# Valve.net
KiCad netlist of a schematic drawn in Altium Designer
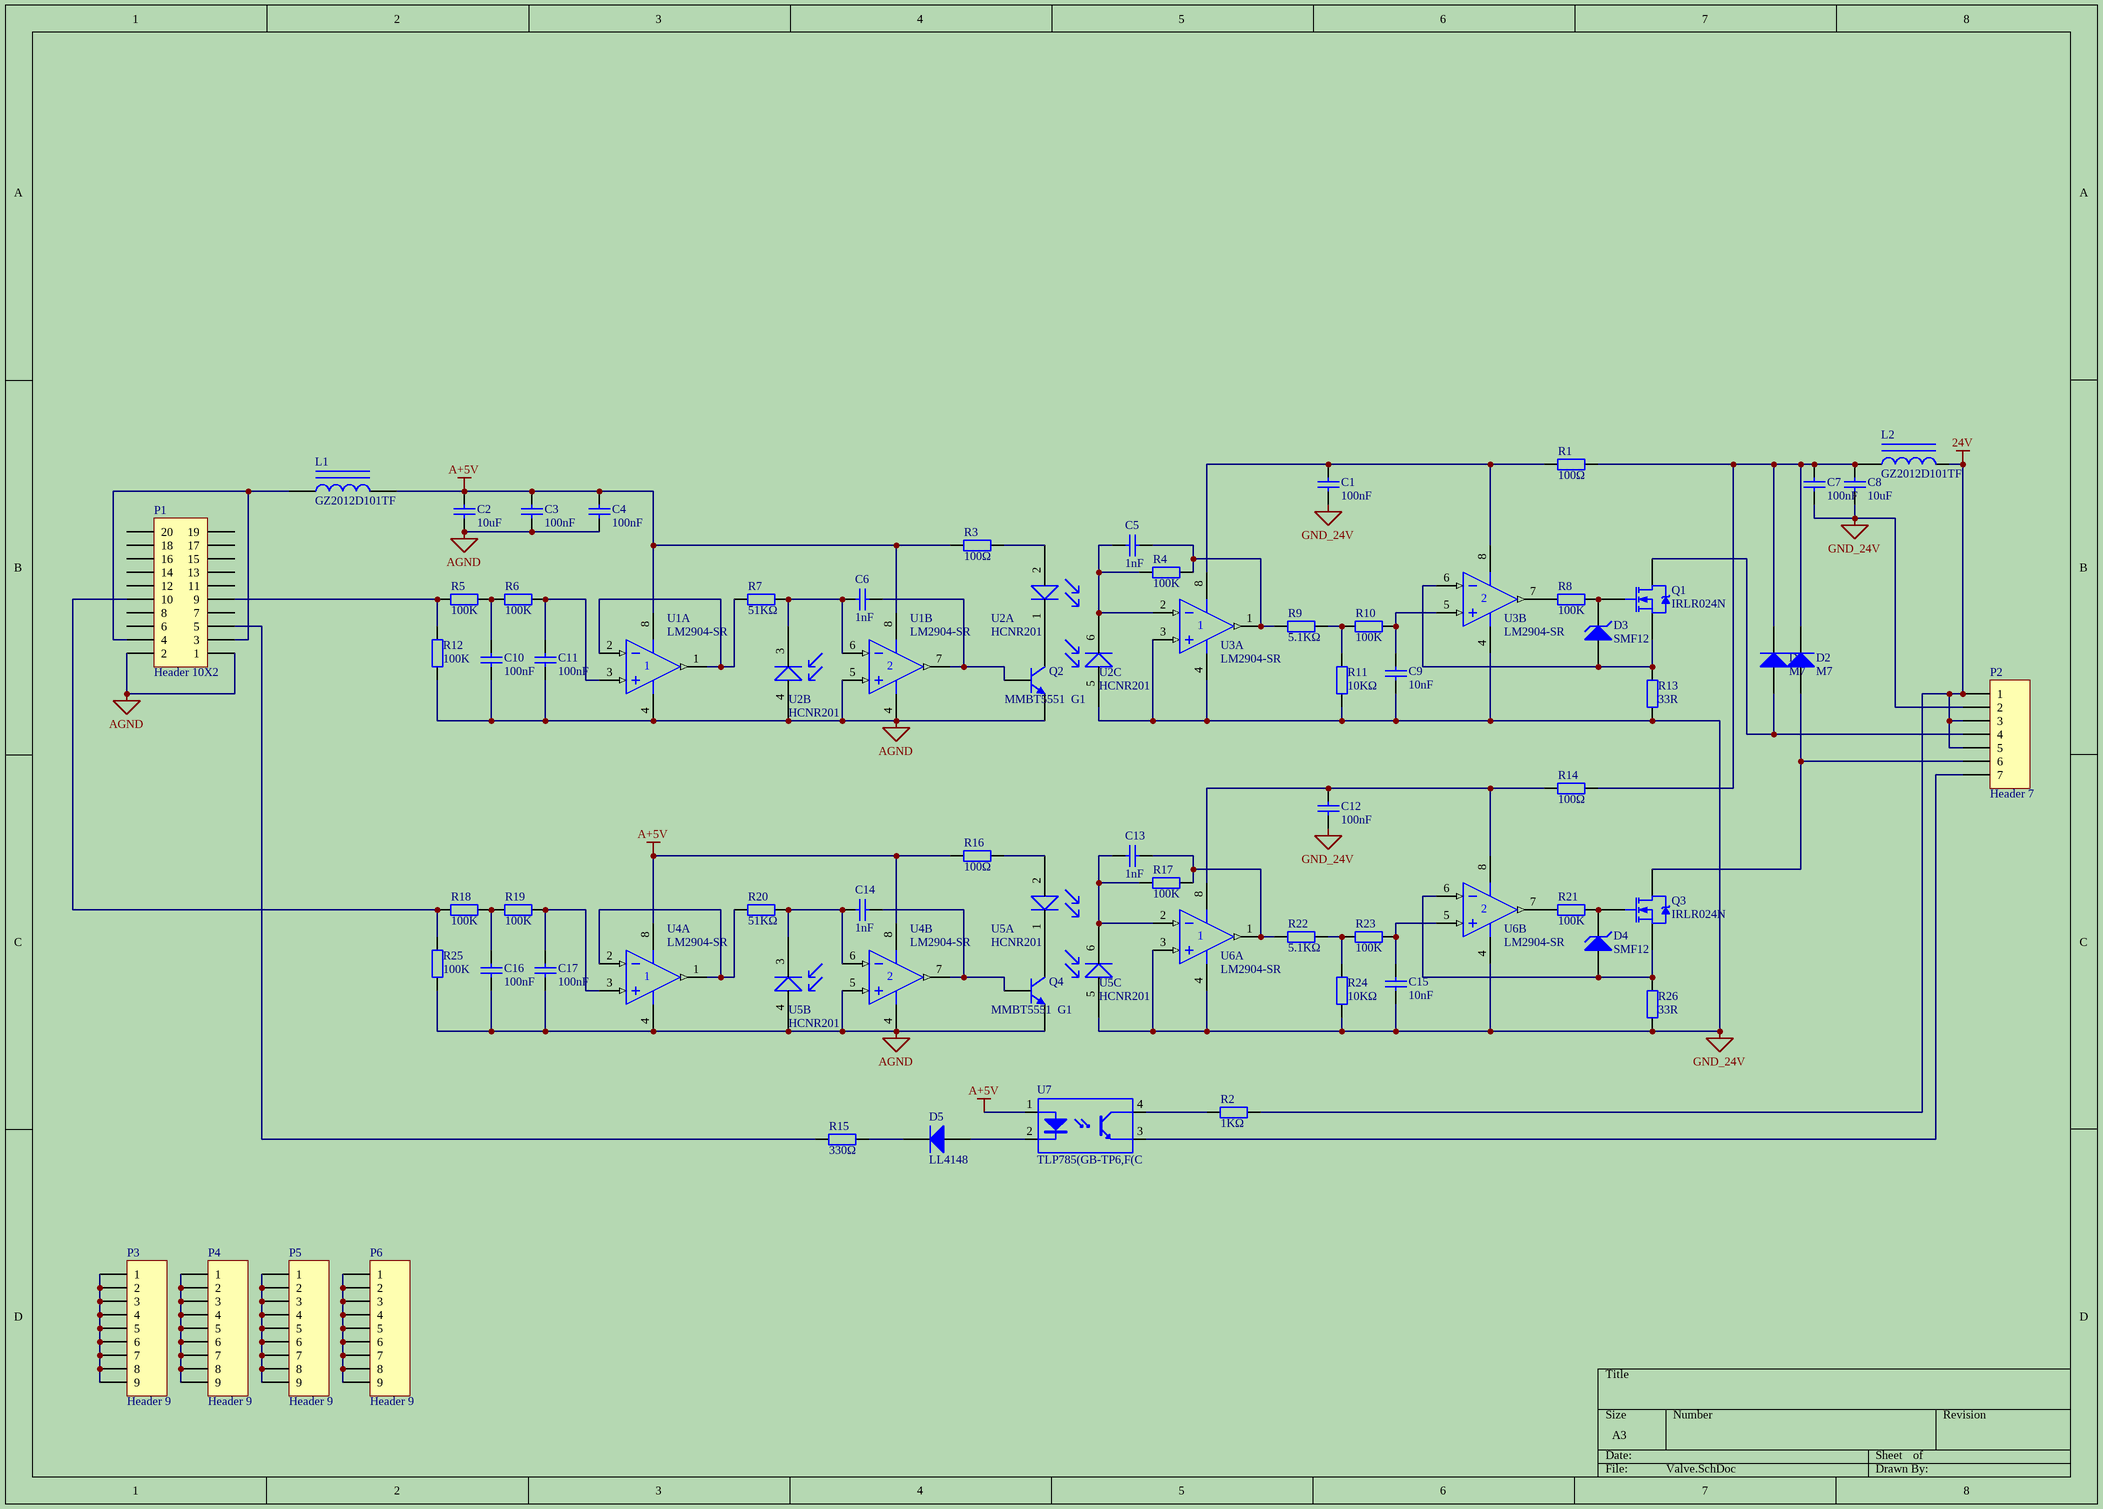
[diagram p0: Valve.SchDoc]

(export (version "E")
  (design (tool "Eeschema 10.0.6"))
  (components
    (comp (ref "C1")
      (value "100nF")
      (footprint "0805_C")
      (description "贴片电容")
      (libsource (lib "Miscellaneous Devices LC") (part "0805 100nF(104) 10% 50V"))
    )
    (comp (ref "C2")
      (value "10uF")
      (footprint "1206_C")
      (description "贴片电容")
      (libsource (lib "Miscellaneous Devices LC") (part "1206 10uF (106) 10% 50V"))
    )
    (comp (ref "C3")
      (value "100nF")
      (footprint "0805_C")
      (description "贴片电容")
      (libsource (lib "Miscellaneous Devices LC") (part "0805 100nF(104) 10% 50V"))
    )
    (comp (ref "C4")
      (value "100nF")
      (footprint "0805_C")
      (description "贴片电容")
      (libsource (lib "Miscellaneous Devices LC") (part "0805 100nF(104) 10% 50V"))
    )
    (comp (ref "C5")
      (value "1nF")
      (footprint "0805_C")
      (description "贴片电容")
      (libsource (lib "Miscellaneous Devices LC") (part "0805 1nF (102) 10% 50V"))
    )
    (comp (ref "C6")
      (value "1nF")
      (footprint "0805_C")
      (description "贴片电容")
      (libsource (lib "Miscellaneous Devices LC") (part "0805 1nF (102) 10% 50V"))
    )
    (comp (ref "C7")
      (value "100nF")
      (footprint "0805_C")
      (description "贴片电容")
      (libsource (lib "Miscellaneous Devices LC") (part "0805 100nF(104) 10% 50V"))
    )
    (comp (ref "C8")
      (value "10uF")
      (footprint "1206_C")
      (description "贴片电容")
      (libsource (lib "Miscellaneous Devices LC") (part "1206 10uF (106) 10% 50V"))
    )
    (comp (ref "C9")
      (value "10nF")
      (footprint "0805_C")
      (description "贴片电容")
      (libsource (lib "Miscellaneous Devices LC") (part "0805 10nF (103) 10% 50V"))
    )
    (comp (ref "C10")
      (value "100nF")
      (footprint "0805_C")
      (description "贴片电容")
      (libsource (lib "Miscellaneous Devices LC") (part "0805 100nF(104) 10% 50V"))
    )
    (comp (ref "C11")
      (value "100nF")
      (footprint "0805_C")
      (description "贴片电容")
      (libsource (lib "Miscellaneous Devices LC") (part "0805 100nF(104) 10% 50V"))
    )
    (comp (ref "C12")
      (value "100nF")
      (footprint "0805_C")
      (description "贴片电容")
      (libsource (lib "Miscellaneous Devices LC") (part "0805 100nF(104) 10% 50V"))
    )
    (comp (ref "C13")
      (value "1nF")
      (footprint "0805_C")
      (description "贴片电容")
      (libsource (lib "Miscellaneous Devices LC") (part "0805 1nF (102) 10% 50V"))
    )
    (comp (ref "C14")
      (value "1nF")
      (footprint "0805_C")
      (description "贴片电容")
      (libsource (lib "Miscellaneous Devices LC") (part "0805 1nF (102) 10% 50V"))
    )
    (comp (ref "C15")
      (value "10nF")
      (footprint "0805_C")
      (description "贴片电容")
      (libsource (lib "Miscellaneous Devices LC") (part "0805 10nF (103) 10% 50V"))
    )
    (comp (ref "C16")
      (value "100nF")
      (footprint "0805_C")
      (description "贴片电容")
      (libsource (lib "Miscellaneous Devices LC") (part "0805 100nF(104) 10% 50V"))
    )
    (comp (ref "C17")
      (value "100nF")
      (footprint "0805_C")
      (description "贴片电容")
      (libsource (lib "Miscellaneous Devices LC") (part "0805 100nF(104) 10% 50V"))
    )
    (comp (ref "D1")
      (value "M7")
      (footprint "SMA(DO-214AC)_S1")
      (description "二极管")
      (libsource (lib "Miscellaneous Devices LC") (part "SMA(DO-214AC) M7"))
    )
    (comp (ref "D2")
      (value "M7")
      (footprint "SMA(DO-214AC)_S1")
      (description "二极管")
      (libsource (lib "Miscellaneous Devices LC") (part "SMA(DO-214AC) M7"))
    )
    (comp (ref "D3")
      (value "SMF12")
      (footprint "SOD-123")
      (description "Zener Diode")
      (fields (field (name "PUBLISHER") "Altium Limited"))
      (libsource (lib "Miscellaneous Devices") (part "D Zener"))
    )
    (comp (ref "D4")
      (value "SMF12")
      (footprint "SOD-123")
      (description "Zener Diode")
      (fields (field (name "PUBLISHER") "Altium Limited"))
      (libsource (lib "Miscellaneous Devices") (part "D Zener"))
    )
    (comp (ref "D5")
      (value "LL4148")
      (footprint "LL-34")
      (description "开关二极管")
      (libsource (lib "Miscellaneous Devices LC") (part "LL-34 LL4148 LL-34 1206"))
    )
    (comp (ref "L1")
      (value "GZ2012D101TF")
      (footprint "0805_L")
      (description "贴片磁珠")
      (libsource (lib "Miscellaneous Devices LC") (part "0805 100Ω 25% 100MHz"))
    )
    (comp (ref "L2")
      (value "GZ2012D101TF")
      (footprint "0805_L")
      (description "贴片磁珠")
      (libsource (lib "Miscellaneous Devices LC") (part "0805 100Ω 25% 100MHz"))
    )
    (comp (ref "P1")
      (value "Header 10X2")
      (footprint "IDC20-EJ")
      (description "Header, 10-Pin, Dual row")
      (fields (field (name "PUBLISHER") "Altium Limited"))
      (libsource (lib "Miscellaneous Connectors") (part "Header 10X2"))
    )
    (comp (ref "P2")
      (value "Header 7")
      (footprint "3.96-7")
      (description "Header, 7-Pin")
      (fields (field (name "PUBLISHER") "Altium Limited"))
      (libsource (lib "Miscellaneous Connectors") (part "Header 7"))
    )
    (comp (ref "P3")
      (value "Header 9")
      (footprint "LK")
      (description "Header, 9-Pin")
      (fields (field (name "PUBLISHER") "Altium Limited"))
      (libsource (lib "Miscellaneous Connectors") (part "Header 9"))
    )
    (comp (ref "P4")
      (value "Header 9")
      (footprint "LK")
      (description "Header, 9-Pin")
      (fields (field (name "PUBLISHER") "Altium Limited"))
      (libsource (lib "Miscellaneous Connectors") (part "Header 9"))
    )
    (comp (ref "P5")
      (value "Header 9")
      (footprint "LK")
      (description "Header, 9-Pin")
      (fields (field (name "PUBLISHER") "Altium Limited"))
      (libsource (lib "Miscellaneous Connectors") (part "Header 9"))
    )
    (comp (ref "P6")
      (value "Header 9")
      (footprint "LK")
      (description "Header, 9-Pin")
      (fields (field (name "PUBLISHER") "Altium Limited"))
      (libsource (lib "Miscellaneous Connectors") (part "Header 9"))
    )
    (comp (ref "Q1")
      (value "IRLR024N")
      (footprint "TO-252AA_N")
      (description "HEXFET Power MOSFET")
      (fields (field (name "PUBLISHER") "Altium Limited"))
      (libsource (lib "IR Discrete MOSFET - Power") (part "IRLR024N"))
    )
    (comp (ref "Q2")
      (value "MMBT5551  G1")
      (footprint "SOT-23(SOT-23-3)")
      (description "三极管")
      (libsource (lib "Miscellaneous Devices LC") (part "SOT-23 MMBT5551  G1"))
    )
    (comp (ref "Q3")
      (value "IRLR024N")
      (footprint "TO-252AA_N")
      (description "HEXFET Power MOSFET")
      (fields (field (name "PUBLISHER") "Altium Limited"))
      (libsource (lib "IR Discrete MOSFET - Power") (part "IRLR024N"))
    )
    (comp (ref "Q4")
      (value "MMBT5551  G1")
      (footprint "SOT-23(SOT-23-3)")
      (description "三极管")
      (libsource (lib "Miscellaneous Devices LC") (part "SOT-23 MMBT5551  G1"))
    )
    (comp (ref "R1")
      (value "100Ω")
      (footprint "0805_R")
      (description "贴片电阻")
      (libsource (lib "Miscellaneous Devices LC") (part "0805 100Ω (1000) 1%"))
    )
    (comp (ref "R2")
      (value "1KΩ")
      (footprint "0805_R")
      (description "贴片电阻")
      (libsource (lib "Miscellaneous Devices LC") (part "0805 1KΩ (1001) 1%"))
    )
    (comp (ref "R3")
      (value "100Ω")
      (footprint "0805_R")
      (description "贴片电阻")
      (libsource (lib "Miscellaneous Devices LC") (part "0805 100Ω (1000) 1%"))
    )
    (comp (ref "R4")
      (value "100K")
      (footprint "0805_R")
      (description "贴片电阻")
      (libsource (lib "Miscellaneous Devices LC") (part "0805 100KΩ (1003) 1%"))
    )
    (comp (ref "R5")
      (value "100K")
      (footprint "0805_R")
      (description "贴片电阻")
      (libsource (lib "Miscellaneous Devices LC") (part "0805 100KΩ (1003) 1%"))
    )
    (comp (ref "R6")
      (value "100K")
      (footprint "0805_R")
      (description "贴片电阻")
      (libsource (lib "Miscellaneous Devices LC") (part "0805 100KΩ (1003) 1%"))
    )
    (comp (ref "R7")
      (value "51KΩ")
      (footprint "0805_R")
      (description "贴片电阻")
      (libsource (lib "Miscellaneous Devices LC") (part "0805 51KΩ (5102) 1%"))
    )
    (comp (ref "R8")
      (value "100K")
      (footprint "0805_R")
      (description "贴片电阻")
      (libsource (lib "Miscellaneous Devices LC") (part "0805 100KΩ (1003) 1%"))
    )
    (comp (ref "R9")
      (value "5.1KΩ")
      (footprint "0805_R")
      (description "贴片电阻")
      (libsource (lib "Miscellaneous Devices LC") (part "0805 5.1KΩ (5101) 1%"))
    )
    (comp (ref "R10")
      (value "100K")
      (footprint "0805_R")
      (description "贴片电阻")
      (libsource (lib "") (part "0805 100KΩ (1003) 1%_1"))
    )
    (comp (ref "R11")
      (value "10KΩ")
      (footprint "0805_R")
      (description "贴片电阻")
      (libsource (lib "Miscellaneous Devices LC") (part "0805 10KΩ (1002) 1%"))
    )
    (comp (ref "R12")
      (value "100K")
      (footprint "0805_R")
      (description "贴片电阻")
      (libsource (lib "") (part "0805 100KΩ (1003) 1%_1"))
    )
    (comp (ref "R13")
      (value "33R")
      (footprint "R2512")
      (description "Resistor")
      (fields (field (name "PUBLISHER") "Altium Limited"))
      (libsource (lib "Miscellaneous Devices") (part "Res2"))
    )
    (comp (ref "R14")
      (value "100Ω")
      (footprint "0805_R")
      (description "贴片电阻")
      (libsource (lib "Miscellaneous Devices LC") (part "0805 100Ω (1000) 1%"))
    )
    (comp (ref "R15")
      (value "330Ω")
      (footprint "0805_R")
      (description "贴片电阻")
      (libsource (lib "Miscellaneous Devices LC") (part "0805 330Ω (3300) 1%"))
    )
    (comp (ref "R16")
      (value "100Ω")
      (footprint "0805_R")
      (description "贴片电阻")
      (libsource (lib "Miscellaneous Devices LC") (part "0805 100Ω (1000) 1%"))
    )
    (comp (ref "R17")
      (value "100K")
      (footprint "0805_R")
      (description "贴片电阻")
      (libsource (lib "Miscellaneous Devices LC") (part "0805 100KΩ (1003) 1%"))
    )
    (comp (ref "R18")
      (value "100K")
      (footprint "0805_R")
      (description "贴片电阻")
      (libsource (lib "Miscellaneous Devices LC") (part "0805 100KΩ (1003) 1%"))
    )
    (comp (ref "R19")
      (value "100K")
      (footprint "0805_R")
      (description "贴片电阻")
      (libsource (lib "Miscellaneous Devices LC") (part "0805 100KΩ (1003) 1%"))
    )
    (comp (ref "R20")
      (value "51KΩ")
      (footprint "0805_R")
      (description "贴片电阻")
      (libsource (lib "Miscellaneous Devices LC") (part "0805 51KΩ (5102) 1%"))
    )
    (comp (ref "R21")
      (value "100K")
      (footprint "0805_R")
      (description "贴片电阻")
      (libsource (lib "Miscellaneous Devices LC") (part "0805 100KΩ (1003) 1%"))
    )
    (comp (ref "R22")
      (value "5.1KΩ")
      (footprint "0805_R")
      (description "贴片电阻")
      (libsource (lib "Miscellaneous Devices LC") (part "0805 5.1KΩ (5101) 1%"))
    )
    (comp (ref "R23")
      (value "100K")
      (footprint "0805_R")
      (description "贴片电阻")
      (libsource (lib "") (part "0805 100KΩ (1003) 1%_1"))
    )
    (comp (ref "R24")
      (value "10KΩ")
      (footprint "0805_R")
      (description "贴片电阻")
      (libsource (lib "Miscellaneous Devices LC") (part "0805 10KΩ (1002) 1%"))
    )
    (comp (ref "R25")
      (value "100K")
      (footprint "0805_R")
      (description "贴片电阻")
      (libsource (lib "") (part "0805 100KΩ (1003) 1%_1"))
    )
    (comp (ref "R26")
      (value "33R")
      (footprint "R2512")
      (description "Resistor")
      (fields (field (name "PUBLISHER") "Altium Limited"))
      (libsource (lib "Miscellaneous Devices") (part "Res2"))
    )
    (comp (ref "U1")
      (value "LM2904-SR")
      (footprint "751-02_N")
      (description "Dual Low-Power Operational Amplifier")
      (fields (field (name "PUBLISHER") "Altium Limited"))
      (libsource (lib "Motorola Amplifier Operational Amplifier") (part "LM2904D"))
    )
    (comp (ref "U2") (value "HCNR201") (footprint "DIP-8-1") (libsource (lib "*") (part "HCNR201")))
    (comp (ref "U3")
      (value "LM2904-SR")
      (footprint "751-02_N")
      (description "Dual Low-Power Operational Amplifier")
      (fields (field (name "PUBLISHER") "Altium Limited"))
      (libsource (lib "Motorola Amplifier Operational Amplifier") (part "LM2904D"))
    )
    (comp (ref "U4")
      (value "LM2904-SR")
      (footprint "751-02_N")
      (description "Dual Low-Power Operational Amplifier")
      (fields (field (name "PUBLISHER") "Altium Limited"))
      (libsource (lib "Motorola Amplifier Operational Amplifier") (part "LM2904D"))
    )
    (comp (ref "U5") (value "HCNR201") (footprint "DIP-8-1") (libsource (lib "*") (part "HCNR201")))
    (comp (ref "U6")
      (value "LM2904-SR")
      (footprint "751-02_N")
      (description "Dual Low-Power Operational Amplifier")
      (fields (field (name "PUBLISHER") "Altium Limited"))
      (libsource (lib "Motorola Amplifier Operational Amplifier") (part "LM2904D"))
    )
    (comp (ref "U7")
      (value "TLP785(GB-TP6,F(C")
      (footprint "TLP785(LF6)")
      (libsource (lib "IC") (part "TLP521"))
    )
  )
  (nets
    (net (code "1") (name "24V") (class "Default")
      (node (ref "L2") (pin "2") (pinfunction "2_2") (pintype "passive"))
      (node (ref "P2") (pin "1") (pinfunction "1_1") (pintype "passive"))
      (node (ref "P2") (pin "3") (pinfunction "3_3") (pintype "passive"))
      (node (ref "P2") (pin "5") (pinfunction "5_5") (pintype "passive"))
      (node (ref "R2") (pin "2") (pinfunction "2_2") (pintype "passive"))
    )
    (net (code "2") (name "A+5V") (class "Default")
      (node (ref "C2") (pin "2") (pinfunction "2_2") (pintype "passive"))
      (node (ref "C3") (pin "2") (pinfunction "2_2") (pintype "passive"))
      (node (ref "C4") (pin "2") (pinfunction "2_2") (pintype "passive"))
      (node (ref "L1") (pin "2") (pinfunction "2_2") (pintype "passive"))
      (node (ref "R16") (pin "2") (pinfunction "2_2") (pintype "passive"))
      (node (ref "R3") (pin "2") (pinfunction "2_2") (pintype "passive"))
      (node (ref "U1") (pin "8") (pinfunction "V+_8") (pintype "power_in"))
      (node (ref "U4") (pin "8") (pinfunction "V+_8") (pintype "power_in"))
      (node (ref "U7") (pin "1") (pinfunction "A_1") (pintype "passive"))
    )
    (net (code "3") (name "AGND") (class "Default")
      (node (ref "C10") (pin "1") (pinfunction "1_1") (pintype "passive"))
      (node (ref "C11") (pin "1") (pinfunction "1_1") (pintype "passive"))
      (node (ref "C16") (pin "1") (pinfunction "1_1") (pintype "passive"))
      (node (ref "C17") (pin "1") (pinfunction "1_1") (pintype "passive"))
      (node (ref "C2") (pin "1") (pinfunction "1_1") (pintype "passive"))
      (node (ref "C3") (pin "1") (pinfunction "1_1") (pintype "passive"))
      (node (ref "C4") (pin "1") (pinfunction "1_1") (pintype "passive"))
      (node (ref "P1") (pin "1") (pinfunction "1_1") (pintype "passive"))
      (node (ref "P1") (pin "2") (pinfunction "2_2") (pintype "passive"))
      (node (ref "Q2") (pin "2") (pinfunction "E_2") (pintype "passive"))
      (node (ref "Q4") (pin "2") (pinfunction "E_2") (pintype "passive"))
      (node (ref "R12") (pin "1") (pinfunction "1_1") (pintype "passive"))
      (node (ref "R25") (pin "1") (pinfunction "1_1") (pintype "passive"))
      (node (ref "U1") (pin "4") (pinfunction "V-_4") (pintype "power_in"))
      (node (ref "U1") (pin "5") (pinfunction "IN+_5") (pintype "input"))
      (node (ref "U2") (pin "4") (pinfunction "+_4") (pintype "passive"))
      (node (ref "U4") (pin "4") (pinfunction "V-_4") (pintype "power_in"))
      (node (ref "U4") (pin "5") (pinfunction "IN+_5") (pintype "input"))
      (node (ref "U5") (pin "4") (pinfunction "+_4") (pintype "passive"))
    )
    (net (code "4") (name "GND_24V") (class "Default")
      (node (ref "C1") (pin "1") (pinfunction "1_1") (pintype "passive"))
      (node (ref "C12") (pin "1") (pinfunction "1_1") (pintype "passive"))
      (node (ref "C15") (pin "1") (pinfunction "1_1") (pintype "passive"))
      (node (ref "C7") (pin "1") (pinfunction "1_1") (pintype "passive"))
      (node (ref "C8") (pin "1") (pinfunction "1_1") (pintype "passive"))
      (node (ref "C9") (pin "1") (pinfunction "1_1") (pintype "passive"))
      (node (ref "P2") (pin "2") (pinfunction "2_2") (pintype "passive"))
      (node (ref "R11") (pin "2") (pinfunction "2_2") (pintype "passive"))
      (node (ref "R13") (pin "1") (pinfunction "1_1") (pintype "passive"))
      (node (ref "R24") (pin "2") (pinfunction "2_2") (pintype "passive"))
      (node (ref "R26") (pin "1") (pinfunction "1_1") (pintype "passive"))
      (node (ref "U2") (pin "5") (pinfunction "+_5") (pintype "passive"))
      (node (ref "U3") (pin "3") (pinfunction "IN+_3") (pintype "input"))
      (node (ref "U3") (pin "4") (pinfunction "V-_4") (pintype "power_in"))
      (node (ref "U5") (pin "5") (pinfunction "+_5") (pintype "passive"))
      (node (ref "U6") (pin "3") (pinfunction "IN+_3") (pintype "input"))
      (node (ref "U6") (pin "4") (pinfunction "V-_4") (pintype "power_in"))
    )
    (net (code "5") (name "Net-(C10-Pad2)") (class "Default")
      (node (ref "C10") (pin "2") (pinfunction "2_2") (pintype "passive"))
      (node (ref "R5") (pin "1") (pinfunction "1_1") (pintype "passive"))
      (node (ref "R6") (pin "2") (pinfunction "2_2") (pintype "passive"))
    )
    (net (code "6") (name "Net-(C16-Pad2)") (class "Default")
      (node (ref "C16") (pin "2") (pinfunction "2_2") (pintype "passive"))
      (node (ref "R18") (pin "1") (pinfunction "1_1") (pintype "passive"))
      (node (ref "R19") (pin "2") (pinfunction "2_2") (pintype "passive"))
    )
    (net (code "7") (name "Net-(D1-A)") (class "Default")
      (node (ref "D1") (pin "1") (pinfunction "A_1") (pintype "passive"))
      (node (ref "P2") (pin "4") (pinfunction "4_4") (pintype "passive"))
      (node (ref "Q1") (pin "4") (pinfunction "D_4") (pintype "passive"))
    )
    (net (code "8") (name "Net-(D1-K)") (class "Default")
      (node (ref "C7") (pin "2") (pinfunction "2_2") (pintype "passive"))
      (node (ref "C8") (pin "2") (pinfunction "2_2") (pintype "passive"))
      (node (ref "D1") (pin "2") (pinfunction "K_2") (pintype "passive"))
      (node (ref "D2") (pin "2") (pinfunction "K_2") (pintype "passive"))
      (node (ref "L2") (pin "1") (pinfunction "1_1") (pintype "passive"))
      (node (ref "R1") (pin "1") (pinfunction "1_1") (pintype "passive"))
      (node (ref "R14") (pin "1") (pinfunction "1_1") (pintype "passive"))
    )
    (net (code "9") (name "Net-(D2-A)") (class "Default")
      (node (ref "D2") (pin "1") (pinfunction "A_1") (pintype "passive"))
      (node (ref "P2") (pin "6") (pinfunction "6_6") (pintype "passive"))
      (node (ref "Q3") (pin "4") (pinfunction "D_4") (pintype "passive"))
    )
    (net (code "10") (name "Net-(D3-A)") (class "Default")
      (node (ref "D3") (pin "1") (pinfunction "A_1") (pintype "passive"))
      (node (ref "Q1") (pin "3") (pinfunction "S_3") (pintype "passive"))
      (node (ref "R13") (pin "2") (pinfunction "2_2") (pintype "passive"))
      (node (ref "U3") (pin "6") (pinfunction "IN-_6") (pintype "input"))
    )
    (net (code "11") (name "Net-(D3-K)") (class "Default")
      (node (ref "D3") (pin "2") (pinfunction "K_2") (pintype "passive"))
      (node (ref "Q1") (pin "1") (pinfunction "G_1") (pintype "passive"))
      (node (ref "R8") (pin "1") (pinfunction "1_1") (pintype "passive"))
    )
    (net (code "12") (name "Net-(D4-A)") (class "Default")
      (node (ref "D4") (pin "1") (pinfunction "A_1") (pintype "passive"))
      (node (ref "Q3") (pin "3") (pinfunction "S_3") (pintype "passive"))
      (node (ref "R26") (pin "2") (pinfunction "2_2") (pintype "passive"))
      (node (ref "U6") (pin "6") (pinfunction "IN-_6") (pintype "input"))
    )
    (net (code "13") (name "Net-(D4-K)") (class "Default")
      (node (ref "D4") (pin "2") (pinfunction "K_2") (pintype "passive"))
      (node (ref "Q3") (pin "1") (pinfunction "G_1") (pintype "passive"))
      (node (ref "R21") (pin "1") (pinfunction "1_1") (pintype "passive"))
    )
    (net (code "14") (name "Net-(D5-A)") (class "Default")
      (node (ref "D5") (pin "1") (pinfunction "A_1") (pintype "passive"))
      (node (ref "U7") (pin "2") (pinfunction "K_2") (pintype "passive"))
    )
    (net (code "15") (name "Net-(D5-K)") (class "Default")
      (node (ref "D5") (pin "2") (pinfunction "K_2") (pintype "passive"))
      (node (ref "R15") (pin "1") (pinfunction "1_1") (pintype "passive"))
    )
    (net (code "16") (name "Net-(L1-Pad1)") (class "Default")
      (node (ref "L1") (pin "1") (pinfunction "1_1") (pintype "passive"))
      (node (ref "P1") (pin "3") (pinfunction "3_3") (pintype "passive"))
      (node (ref "P1") (pin "4") (pinfunction "4_4") (pintype "passive"))
    )
    (net (code "17") (name "Net-(P1-Pad5)") (class "Default")
      (node (ref "P1") (pin "5") (pinfunction "5_5") (pintype "passive"))
      (node (ref "R15") (pin "2") (pinfunction "2_2") (pintype "passive"))
    )
    (net (code "18") (name "Net-(P1-Pad9)") (class "Default")
      (node (ref "P1") (pin "9") (pinfunction "9_9") (pintype "passive"))
      (node (ref "R12") (pin "2") (pinfunction "2_2") (pintype "passive"))
      (node (ref "R5") (pin "2") (pinfunction "2_2") (pintype "passive"))
    )
    (net (code "19") (name "Net-(P1-Pad10)") (class "Default")
      (node (ref "P1") (pin "10") (pinfunction "10_10") (pintype "passive"))
      (node (ref "R18") (pin "2") (pinfunction "2_2") (pintype "passive"))
      (node (ref "R25") (pin "2") (pinfunction "2_2") (pintype "passive"))
    )
    (net (code "20") (name "Net-(P3-Pad1)") (class "Default")
      (node (ref "P3") (pin "1") (pinfunction "1_1") (pintype "passive"))
      (node (ref "P3") (pin "2") (pinfunction "2_2") (pintype "passive"))
      (node (ref "P3") (pin "3") (pinfunction "3_3") (pintype "passive"))
      (node (ref "P3") (pin "4") (pinfunction "4_4") (pintype "passive"))
      (node (ref "P3") (pin "5") (pinfunction "5_5") (pintype "passive"))
      (node (ref "P3") (pin "6") (pinfunction "6_6") (pintype "passive"))
      (node (ref "P3") (pin "7") (pinfunction "7_7") (pintype "passive"))
      (node (ref "P3") (pin "8") (pinfunction "8_8") (pintype "passive"))
      (node (ref "P3") (pin "9") (pinfunction "9_9") (pintype "passive"))
    )
    (net (code "21") (name "Net-(P4-Pad1)") (class "Default")
      (node (ref "P4") (pin "1") (pinfunction "1_1") (pintype "passive"))
      (node (ref "P4") (pin "2") (pinfunction "2_2") (pintype "passive"))
      (node (ref "P4") (pin "3") (pinfunction "3_3") (pintype "passive"))
      (node (ref "P4") (pin "4") (pinfunction "4_4") (pintype "passive"))
      (node (ref "P4") (pin "5") (pinfunction "5_5") (pintype "passive"))
      (node (ref "P4") (pin "6") (pinfunction "6_6") (pintype "passive"))
      (node (ref "P4") (pin "7") (pinfunction "7_7") (pintype "passive"))
      (node (ref "P4") (pin "8") (pinfunction "8_8") (pintype "passive"))
      (node (ref "P4") (pin "9") (pinfunction "9_9") (pintype "passive"))
    )
    (net (code "22") (name "Net-(P5-Pad1)") (class "Default")
      (node (ref "P5") (pin "1") (pinfunction "1_1") (pintype "passive"))
      (node (ref "P5") (pin "2") (pinfunction "2_2") (pintype "passive"))
      (node (ref "P5") (pin "3") (pinfunction "3_3") (pintype "passive"))
      (node (ref "P5") (pin "4") (pinfunction "4_4") (pintype "passive"))
      (node (ref "P5") (pin "5") (pinfunction "5_5") (pintype "passive"))
      (node (ref "P5") (pin "6") (pinfunction "6_6") (pintype "passive"))
      (node (ref "P5") (pin "7") (pinfunction "7_7") (pintype "passive"))
      (node (ref "P5") (pin "8") (pinfunction "8_8") (pintype "passive"))
      (node (ref "P5") (pin "9") (pinfunction "9_9") (pintype "passive"))
    )
    (net (code "23") (name "Net-(P6-Pad1)") (class "Default")
      (node (ref "P6") (pin "1") (pinfunction "1_1") (pintype "passive"))
      (node (ref "P6") (pin "2") (pinfunction "2_2") (pintype "passive"))
      (node (ref "P6") (pin "3") (pinfunction "3_3") (pintype "passive"))
      (node (ref "P6") (pin "4") (pinfunction "4_4") (pintype "passive"))
      (node (ref "P6") (pin "5") (pinfunction "5_5") (pintype "passive"))
      (node (ref "P6") (pin "6") (pinfunction "6_6") (pintype "passive"))
      (node (ref "P6") (pin "7") (pinfunction "7_7") (pintype "passive"))
      (node (ref "P6") (pin "8") (pinfunction "8_8") (pintype "passive"))
      (node (ref "P6") (pin "9") (pinfunction "9_9") (pintype "passive"))
    )
    (net (code "24") (name "Net-(Q2-B)") (class "Default")
      (node (ref "C6") (pin "1") (pinfunction "1_1") (pintype "passive"))
      (node (ref "Q2") (pin "1") (pinfunction "B_1") (pintype "passive"))
      (node (ref "U1") (pin "7") (pinfunction "OUT_7") (pintype "output"))
    )
    (net (code "25") (name "Net-(Q2-C)") (class "Default")
      (node (ref "Q2") (pin "3") (pinfunction "C_3") (pintype "passive"))
      (node (ref "U2") (pin "1") (pinfunction "-_1") (pintype "passive"))
    )
    (net (code "26") (name "Net-(Q4-B)") (class "Default")
      (node (ref "C14") (pin "1") (pinfunction "1_1") (pintype "passive"))
      (node (ref "Q4") (pin "1") (pinfunction "B_1") (pintype "passive"))
      (node (ref "U4") (pin "7") (pinfunction "OUT_7") (pintype "output"))
    )
    (net (code "27") (name "Net-(Q4-C)") (class "Default")
      (node (ref "Q4") (pin "3") (pinfunction "C_3") (pintype "passive"))
      (node (ref "U5") (pin "1") (pinfunction "-_1") (pintype "passive"))
    )
    (net (code "28") (name "Net-(R10-Pad1)") (class "Default")
      (node (ref "R10") (pin "1") (pinfunction "1_1") (pintype "passive"))
      (node (ref "R11") (pin "1") (pinfunction "1_1") (pintype "passive"))
      (node (ref "R9") (pin "1") (pinfunction "1_1") (pintype "passive"))
    )
    (net (code "29") (name "Net-(R22-Pad1)") (class "Default")
      (node (ref "R22") (pin "1") (pinfunction "1_1") (pintype "passive"))
      (node (ref "R23") (pin "1") (pinfunction "1_1") (pintype "passive"))
      (node (ref "R24") (pin "1") (pinfunction "1_1") (pintype "passive"))
    )
    (net (code "30") (name "Net-(U1A-IN+)") (class "Default")
      (node (ref "C11") (pin "2") (pinfunction "2_2") (pintype "passive"))
      (node (ref "R6") (pin "1") (pinfunction "1_1") (pintype "passive"))
      (node (ref "U1") (pin "3") (pinfunction "IN+_3") (pintype "input"))
    )
    (net (code "31") (name "Net-(U1A-IN-)") (class "Default")
      (node (ref "R7") (pin "2") (pinfunction "2_2") (pintype "passive"))
      (node (ref "U1") (pin "1") (pinfunction "OUT_1") (pintype "output"))
      (node (ref "U1") (pin "2") (pinfunction "IN-_2") (pintype "input"))
    )
    (net (code "32") (name "Net-(U1B-IN-)") (class "Default")
      (node (ref "C6") (pin "2") (pinfunction "2_2") (pintype "passive"))
      (node (ref "R7") (pin "1") (pinfunction "1_1") (pintype "passive"))
      (node (ref "U1") (pin "6") (pinfunction "IN-_6") (pintype "input"))
      (node (ref "U2") (pin "3") (pinfunction "-_3") (pintype "passive"))
    )
    (net (code "33") (name "Net-(U2A-+)") (class "Default")
      (node (ref "R3") (pin "1") (pinfunction "1_1") (pintype "passive"))
      (node (ref "U2") (pin "2") (pinfunction "+_2") (pintype "passive"))
    )
    (net (code "34") (name "Net-(U2C--)") (class "Default")
      (node (ref "C5") (pin "2") (pinfunction "2_2") (pintype "passive"))
      (node (ref "R4") (pin "2") (pinfunction "2_2") (pintype "passive"))
      (node (ref "U2") (pin "6") (pinfunction "-_6") (pintype "passive"))
      (node (ref "U3") (pin "2") (pinfunction "IN-_2") (pintype "input"))
    )
    (net (code "35") (name "Net-(U3A-OUT)") (class "Default")
      (node (ref "C5") (pin "1") (pinfunction "1_1") (pintype "passive"))
      (node (ref "R4") (pin "1") (pinfunction "1_1") (pintype "passive"))
      (node (ref "R9") (pin "2") (pinfunction "2_2") (pintype "passive"))
      (node (ref "U3") (pin "1") (pinfunction "OUT_1") (pintype "output"))
    )
    (net (code "36") (name "Net-(U3A-V+)") (class "Default")
      (node (ref "C1") (pin "2") (pinfunction "2_2") (pintype "passive"))
      (node (ref "R1") (pin "2") (pinfunction "2_2") (pintype "passive"))
      (node (ref "U3") (pin "8") (pinfunction "V+_8") (pintype "power_in"))
    )
    (net (code "37") (name "Net-(U3B-IN+)") (class "Default")
      (node (ref "C9") (pin "2") (pinfunction "2_2") (pintype "passive"))
      (node (ref "R10") (pin "2") (pinfunction "2_2") (pintype "passive"))
      (node (ref "U3") (pin "5") (pinfunction "IN+_5") (pintype "input"))
    )
    (net (code "38") (name "Net-(U3B-OUT)") (class "Default")
      (node (ref "R8") (pin "2") (pinfunction "2_2") (pintype "passive"))
      (node (ref "U3") (pin "7") (pinfunction "OUT_7") (pintype "output"))
    )
    (net (code "39") (name "Net-(U4A-IN+)") (class "Default")
      (node (ref "C17") (pin "2") (pinfunction "2_2") (pintype "passive"))
      (node (ref "R19") (pin "1") (pinfunction "1_1") (pintype "passive"))
      (node (ref "U4") (pin "3") (pinfunction "IN+_3") (pintype "input"))
    )
    (net (code "40") (name "Net-(U4A-IN-)") (class "Default")
      (node (ref "R20") (pin "2") (pinfunction "2_2") (pintype "passive"))
      (node (ref "U4") (pin "1") (pinfunction "OUT_1") (pintype "output"))
      (node (ref "U4") (pin "2") (pinfunction "IN-_2") (pintype "input"))
    )
    (net (code "41") (name "Net-(U4B-IN-)") (class "Default")
      (node (ref "C14") (pin "2") (pinfunction "2_2") (pintype "passive"))
      (node (ref "R20") (pin "1") (pinfunction "1_1") (pintype "passive"))
      (node (ref "U4") (pin "6") (pinfunction "IN-_6") (pintype "input"))
      (node (ref "U5") (pin "3") (pinfunction "-_3") (pintype "passive"))
    )
    (net (code "42") (name "Net-(U5A-+)") (class "Default")
      (node (ref "R16") (pin "1") (pinfunction "1_1") (pintype "passive"))
      (node (ref "U5") (pin "2") (pinfunction "+_2") (pintype "passive"))
    )
    (net (code "43") (name "Net-(U5C--)") (class "Default")
      (node (ref "C13") (pin "2") (pinfunction "2_2") (pintype "passive"))
      (node (ref "R17") (pin "2") (pinfunction "2_2") (pintype "passive"))
      (node (ref "U5") (pin "6") (pinfunction "-_6") (pintype "passive"))
      (node (ref "U6") (pin "2") (pinfunction "IN-_2") (pintype "input"))
    )
    (net (code "44") (name "Net-(U6A-OUT)") (class "Default")
      (node (ref "C13") (pin "1") (pinfunction "1_1") (pintype "passive"))
      (node (ref "R17") (pin "1") (pinfunction "1_1") (pintype "passive"))
      (node (ref "R22") (pin "2") (pinfunction "2_2") (pintype "passive"))
      (node (ref "U6") (pin "1") (pinfunction "OUT_1") (pintype "output"))
    )
    (net (code "45") (name "Net-(U6A-V+)") (class "Default")
      (node (ref "C12") (pin "2") (pinfunction "2_2") (pintype "passive"))
      (node (ref "R14") (pin "2") (pinfunction "2_2") (pintype "passive"))
      (node (ref "U6") (pin "8") (pinfunction "V+_8") (pintype "power_in"))
    )
    (net (code "46") (name "Net-(U6B-IN+)") (class "Default")
      (node (ref "C15") (pin "2") (pinfunction "2_2") (pintype "passive"))
      (node (ref "R23") (pin "2") (pinfunction "2_2") (pintype "passive"))
      (node (ref "U6") (pin "5") (pinfunction "IN+_5") (pintype "input"))
    )
    (net (code "47") (name "Net-(U6B-OUT)") (class "Default")
      (node (ref "R21") (pin "2") (pinfunction "2_2") (pintype "passive"))
      (node (ref "U6") (pin "7") (pinfunction "OUT_7") (pintype "output"))
    )
    (net (code "48") (name "Net-(U7-C)") (class "Default")
      (node (ref "R2") (pin "1") (pinfunction "1_1") (pintype "passive"))
      (node (ref "U7") (pin "4") (pinfunction "C_4") (pintype "passive"))
    )
    (net (code "49") (name "Net-(U7-E)") (class "Default")
      (node (ref "P2") (pin "7") (pinfunction "7_7") (pintype "passive"))
      (node (ref "U7") (pin "3") (pinfunction "E_3") (pintype "passive"))
    )
    (net (code "50") (name "unconnected-(P1-Pad6)") (class "Default")
      (node (ref "P1") (pin "6") (pinfunction "6_6") (pintype "passive"))
    )
    (net (code "51") (name "unconnected-(P1-Pad7)") (class "Default")
      (node (ref "P1") (pin "7") (pinfunction "7_7") (pintype "passive"))
    )
    (net (code "52") (name "unconnected-(P1-Pad8)") (class "Default")
      (node (ref "P1") (pin "8") (pinfunction "8_8") (pintype "passive"))
    )
    (net (code "53") (name "unconnected-(P1-Pad11)") (class "Default")
      (node (ref "P1") (pin "11") (pinfunction "11_11") (pintype "passive"))
    )
    (net (code "54") (name "unconnected-(P1-Pad12)") (class "Default")
      (node (ref "P1") (pin "12") (pinfunction "12_12") (pintype "passive"))
    )
    (net (code "55") (name "unconnected-(P1-Pad13)") (class "Default")
      (node (ref "P1") (pin "13") (pinfunction "13_13") (pintype "passive"))
    )
    (net (code "56") (name "unconnected-(P1-Pad14)") (class "Default")
      (node (ref "P1") (pin "14") (pinfunction "14_14") (pintype "passive"))
    )
    (net (code "57") (name "unconnected-(P1-Pad15)") (class "Default")
      (node (ref "P1") (pin "15") (pinfunction "15_15") (pintype "passive"))
    )
    (net (code "58") (name "unconnected-(P1-Pad16)") (class "Default")
      (node (ref "P1") (pin "16") (pinfunction "16_16") (pintype "passive"))
    )
    (net (code "59") (name "unconnected-(P1-Pad17)") (class "Default")
      (node (ref "P1") (pin "17") (pinfunction "17_17") (pintype "passive"))
    )
    (net (code "60") (name "unconnected-(P1-Pad18)") (class "Default")
      (node (ref "P1") (pin "18") (pinfunction "18_18") (pintype "passive"))
    )
    (net (code "61") (name "unconnected-(P1-Pad19)") (class "Default")
      (node (ref "P1") (pin "19") (pinfunction "19_19") (pintype "passive"))
    )
    (net (code "62") (name "unconnected-(P1-Pad20)") (class "Default")
      (node (ref "P1") (pin "20") (pinfunction "20_20") (pintype "passive"))
    )
  )
)
